# 06_POWER_2.net
KiCad netlist of a schematic drawn in Altium Designer
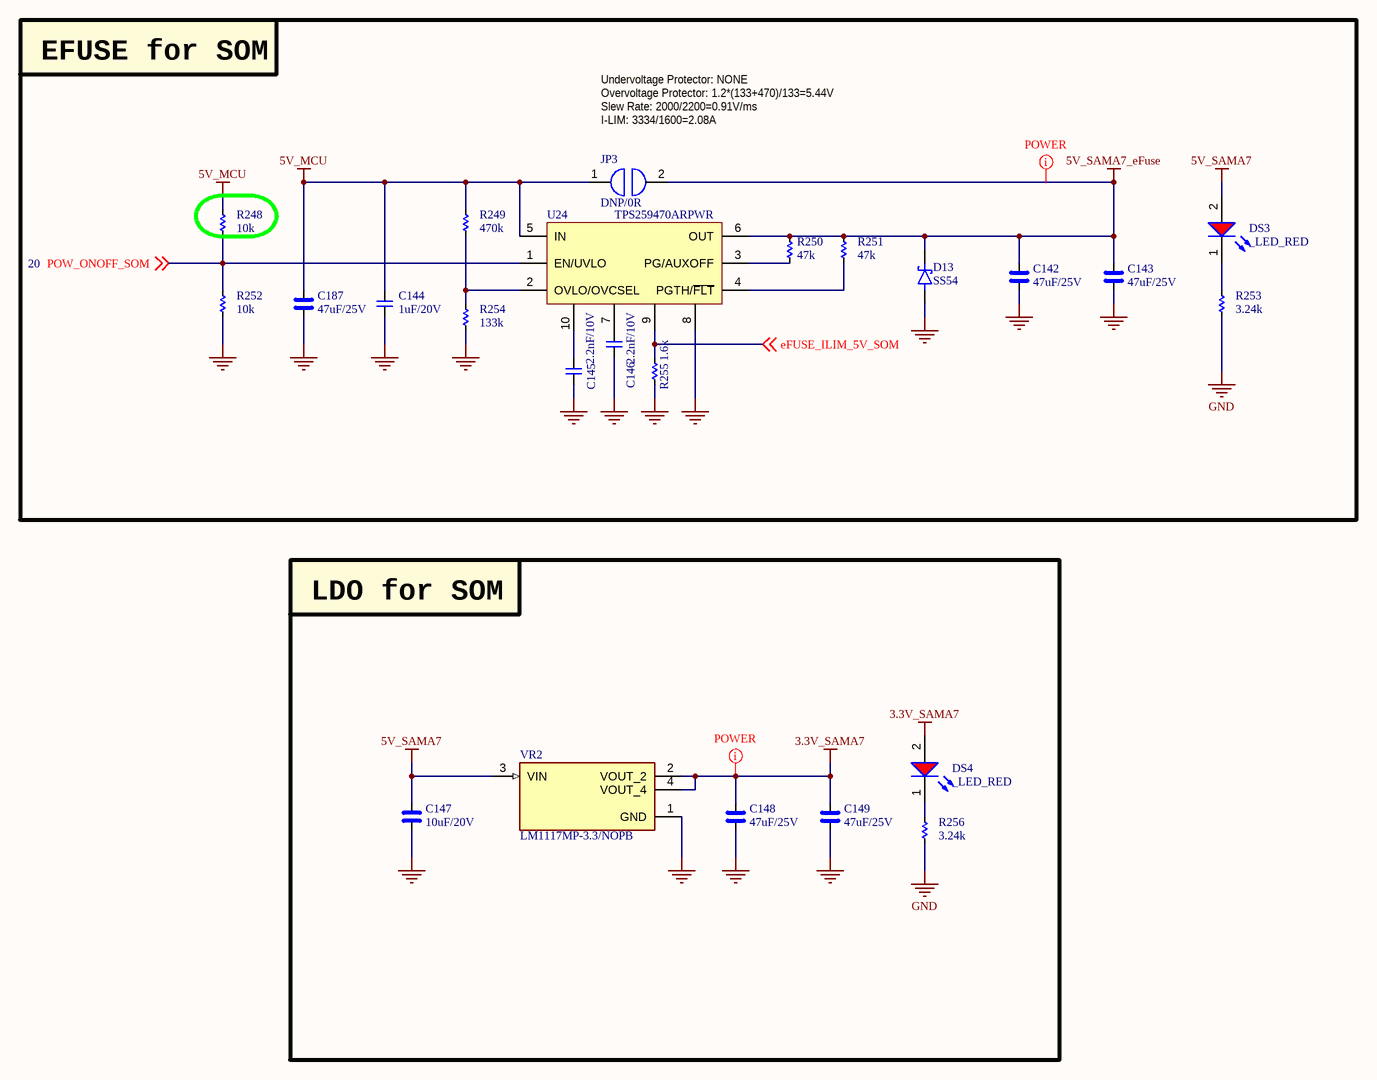
[diagram p0: 06_POWER_2.SchDoc]

(export (version "E")
  (design (tool "Eeschema 10.0.6"))
  (components
    (comp (ref "C142")
      (value "47uF/25V")
      (footprint "CAP_C_3225X80")
      (description "CAP High Value")
      (libsource (lib "LABLIB") (part "_CAP_C_High_2"))
    )
    (comp (ref "C143")
      (value "47uF/25V")
      (footprint "CAP_C_3225X80")
      (description "CAP High Value")
      (libsource (lib "LABLIB") (part "_CAP_C_High_2"))
    )
    (comp (ref "C144")
      (value "1uF/20V")
      (footprint "CAP_C_1005X60")
      (description "CAP")
      (libsource (lib "LABLIB") (part "_CAP_C_2"))
    )
    (comp (ref "C145")
      (value "2.2nF/10V")
      (footprint "CAP_C_1005X60")
      (description "CAP")
      (libsource (lib "LABLIB") (part "_CAP_C_2"))
    )
    (comp (ref "C146")
      (value "2.2nF/10V")
      (footprint "CAP_C_1005X60")
      (description "CAP")
      (libsource (lib "LABLIB") (part "_CAP_C_2"))
    )
    (comp (ref "C147")
      (value "10uF/20V")
      (footprint "CAP_C_2012X110")
      (description "CAP High Value")
      (libsource (lib "LABLIB") (part "_CAP_C_High_2"))
    )
    (comp (ref "C148")
      (value "47uF/25V")
      (footprint "CAP_C_3225X80")
      (description "CAP High Value")
      (libsource (lib "LABLIB") (part "_CAP_C_High_2"))
    )
    (comp (ref "C149")
      (value "47uF/25V")
      (footprint "CAP_C_3225X80")
      (description "CAP High Value")
      (libsource (lib "LABLIB") (part "_CAP_C_High_2"))
    )
    (comp (ref "C187")
      (value "47uF/25V")
      (footprint "CAP_C_3225X80")
      (description "CAP High Value")
      (libsource (lib "LABLIB") (part "_CAP_C_High_2"))
    )
    (comp (ref "D13")
      (value "SS54")
      (footprint "DO-214AC_SMA")
      (description "DIODE SCHOTTKY")
      (libsource (lib "LABLIB") (part "DIODE SCHOTTKY"))
    )
    (comp (ref "DS3") (value "_LED_RED") (footprint "LED_0603") (libsource (lib "LABLIB") (part "_LED_RED")))
    (comp (ref "DS4") (value "_LED_RED") (footprint "LED_0603") (libsource (lib "LABLIB") (part "_LED_RED")))
    (comp (ref "JP3") (value "DNP/0R") (footprint "JUMPER_1608") (libsource (lib "EXP_V1") (part "JUMPER")))
    (comp (ref "R248")
      (value "10k")
      (footprint "RES_C_1005X40")
      (description "RES")
      (libsource (lib "LABLIB") (part "_RES_B_2"))
    )
    (comp (ref "R249")
      (value "470k")
      (footprint "RES_C_1005X40")
      (description "RES")
      (libsource (lib "LABLIB") (part "_RES_B_2"))
    )
    (comp (ref "R250")
      (value "47k")
      (footprint "RES_C_1005X40")
      (description "RES")
      (libsource (lib "LABLIB") (part "_RES_B_2"))
    )
    (comp (ref "R251")
      (value "47k")
      (footprint "RES_C_1005X40")
      (description "RES")
      (libsource (lib "LABLIB") (part "_RES_B_2"))
    )
    (comp (ref "R252")
      (value "10k")
      (footprint "RES_C_1005X40")
      (description "RES")
      (libsource (lib "LABLIB") (part "_RES_B_2"))
    )
    (comp (ref "R253")
      (value "3.24k")
      (footprint "RES_C_1005X40")
      (description "RES")
      (libsource (lib "LABLIB") (part "_RES_B_2"))
    )
    (comp (ref "R254")
      (value "133k")
      (footprint "RES_C_1005X40")
      (description "RES")
      (libsource (lib "LABLIB") (part "_RES_B_2"))
    )
    (comp (ref "R255")
      (value "1.6k")
      (footprint "RES_C_1005X40")
      (description "RES")
      (libsource (lib "LABLIB") (part "_RES_B_2"))
    )
    (comp (ref "R256")
      (value "3.24k")
      (footprint "RES_C_1005X40")
      (description "RES")
      (libsource (lib "LABLIB") (part "_RES_B_2"))
    )
    (comp (ref "U24")
      (value "TPS259470ARPWR")
      (footprint "VQFN-HR-10")
      (libsource (lib "EXP_HW_V3") (part "TPS259470ARPWR"))
    )
    (comp (ref "VR2")
      (value "LM1117MP-3.3/NOPB")
      (footprint "VREG_LM1117MP-3.3/NOPB")
      (description "800-mA 15-V linear voltage regulator")
      (fields (field (name "MF") "Texas Instruments"))
      (libsource (lib "LABLIB") (part "LM1117MP-3.3/NOPB"))
    )
  )
  (nets
    (net (code "1") (name "3.3V_SAMA7") (class "Default")
      (node (ref "C148") (pin "2") (pinfunction "2_2") (pintype "passive"))
      (node (ref "C149") (pin "2") (pinfunction "2_2") (pintype "passive"))
      (node (ref "DS4") (pin "2") (pinfunction "A_2") (pintype "passive"))
      (node (ref "VR2") (pin "2") (pinfunction "VOUT_2_2") (pintype "power_in"))
      (node (ref "VR2") (pin "4") (pinfunction "VOUT_4_4") (pintype "power_in"))
    )
    (net (code "2") (name "5V_MCU") (class "Default")
      (node (ref "C144") (pin "2") (pinfunction "2_2") (pintype "passive"))
      (node (ref "C187") (pin "2") (pinfunction "2_2") (pintype "passive"))
      (node (ref "JP3") (pin "1") (pinfunction "1_1") (pintype "passive"))
      (node (ref "R248") (pin "1") (pinfunction "1_1") (pintype "passive"))
      (node (ref "R249") (pin "2") (pinfunction "2_2") (pintype "passive"))
      (node (ref "U24") (pin "5") (pinfunction "IN_5") (pintype "passive"))
    )
    (net (code "3") (name "5V_SAMA7") (class "Default")
      (node (ref "C147") (pin "1") (pinfunction "1_1") (pintype "passive"))
      (node (ref "DS3") (pin "2") (pinfunction "A_2") (pintype "passive"))
      (node (ref "VR2") (pin "3") (pinfunction "VIN_3") (pintype "input"))
    )
    (net (code "4") (name "5V_SAMA7_eFuse") (class "Default")
      (node (ref "C142") (pin "2") (pinfunction "2_2") (pintype "passive"))
      (node (ref "C143") (pin "2") (pinfunction "2_2") (pintype "passive"))
      (node (ref "D13") (pin "1") (pinfunction "K_1") (pintype "passive"))
      (node (ref "JP3") (pin "2") (pinfunction "2_2") (pintype "passive"))
      (node (ref "R250") (pin "2") (pinfunction "2_2") (pintype "passive"))
      (node (ref "R251") (pin "2") (pinfunction "2_2") (pintype "passive"))
      (node (ref "U24") (pin "6") (pinfunction "OUT_6") (pintype "passive"))
    )
    (net (code "5") (name "GND") (class "Default")
      (node (ref "C142") (pin "1") (pinfunction "1_1") (pintype "passive"))
      (node (ref "C143") (pin "1") (pinfunction "1_1") (pintype "passive"))
      (node (ref "C144") (pin "1") (pinfunction "1_1") (pintype "passive"))
      (node (ref "C145") (pin "1") (pinfunction "1_1") (pintype "passive"))
      (node (ref "C146") (pin "1") (pinfunction "1_1") (pintype "passive"))
      (node (ref "C147") (pin "2") (pinfunction "2_2") (pintype "passive"))
      (node (ref "C148") (pin "1") (pinfunction "1_1") (pintype "passive"))
      (node (ref "C149") (pin "1") (pinfunction "1_1") (pintype "passive"))
      (node (ref "C187") (pin "1") (pinfunction "1_1") (pintype "passive"))
      (node (ref "D13") (pin "2") (pinfunction "A_2") (pintype "passive"))
      (node (ref "R252") (pin "2") (pinfunction "2_2") (pintype "passive"))
      (node (ref "R253") (pin "1") (pinfunction "1_1") (pintype "passive"))
      (node (ref "R254") (pin "1") (pinfunction "1_1") (pintype "passive"))
      (node (ref "R255") (pin "1") (pinfunction "1_1") (pintype "passive"))
      (node (ref "R256") (pin "1") (pinfunction "1_1") (pintype "passive"))
      (node (ref "U24") (pin "8") (pinfunction "8_8") (pintype "passive"))
      (node (ref "VR2") (pin "1") (pinfunction "GND_1") (pintype "power_in"))
    )
    (net (code "6") (name "Net-(C145-Pad2)") (class "Default")
      (node (ref "C145") (pin "2") (pinfunction "2_2") (pintype "passive"))
      (node (ref "U24") (pin "10") (pinfunction "10_10") (pintype "passive"))
    )
    (net (code "7") (name "Net-(C146-Pad2)") (class "Default")
      (node (ref "C146") (pin "2") (pinfunction "2_2") (pintype "passive"))
      (node (ref "U24") (pin "7") (pinfunction "7_7") (pintype "passive"))
    )
    (net (code "8") (name "Net-(DS3-K)") (class "Default")
      (node (ref "DS3") (pin "1") (pinfunction "K_1") (pintype "passive"))
      (node (ref "R253") (pin "2") (pinfunction "2_2") (pintype "passive"))
    )
    (net (code "9") (name "Net-(DS4-K)") (class "Default")
      (node (ref "DS4") (pin "1") (pinfunction "K_1") (pintype "passive"))
      (node (ref "R256") (pin "2") (pinfunction "2_2") (pintype "passive"))
    )
    (net (code "10") (name "Net-(U24-OVLO{slash}OVCSEL)") (class "Default")
      (node (ref "R249") (pin "1") (pinfunction "1_1") (pintype "passive"))
      (node (ref "R254") (pin "2") (pinfunction "2_2") (pintype "passive"))
      (node (ref "U24") (pin "2") (pinfunction "OVLO/OVCSEL_2") (pintype "passive"))
    )
    (net (code "11") (name "Net-(U24-PGTH{slash}~{FLT})") (class "Default")
      (node (ref "R251") (pin "1") (pinfunction "1_1") (pintype "passive"))
      (node (ref "U24") (pin "4") (pinfunction "PGTH/~{FLT}_4") (pintype "passive"))
    )
    (net (code "12") (name "Net-(U24-PG{slash}AUXOFF)") (class "Default")
      (node (ref "R250") (pin "1") (pinfunction "1_1") (pintype "passive"))
      (node (ref "U24") (pin "3") (pinfunction "PG/AUXOFF_3") (pintype "passive"))
    )
    (net (code "13") (name "POW_ONOFF_SOM") (class "Default")
      (node (ref "R248") (pin "2") (pinfunction "2_2") (pintype "passive"))
      (node (ref "R252") (pin "1") (pinfunction "1_1") (pintype "passive"))
      (node (ref "U24") (pin "1") (pinfunction "EN/UVLO_1") (pintype "passive"))
    )
    (net (code "14") (name "eFUSE_ILIM_5V_SOM") (class "Default")
      (node (ref "R255") (pin "2") (pinfunction "2_2") (pintype "passive"))
      (node (ref "U24") (pin "9") (pinfunction "9_9") (pintype "passive"))
    )
  )
)
